# auxshiled1_8b.net
KiCad netlist of a schematic drawn in EAGLE
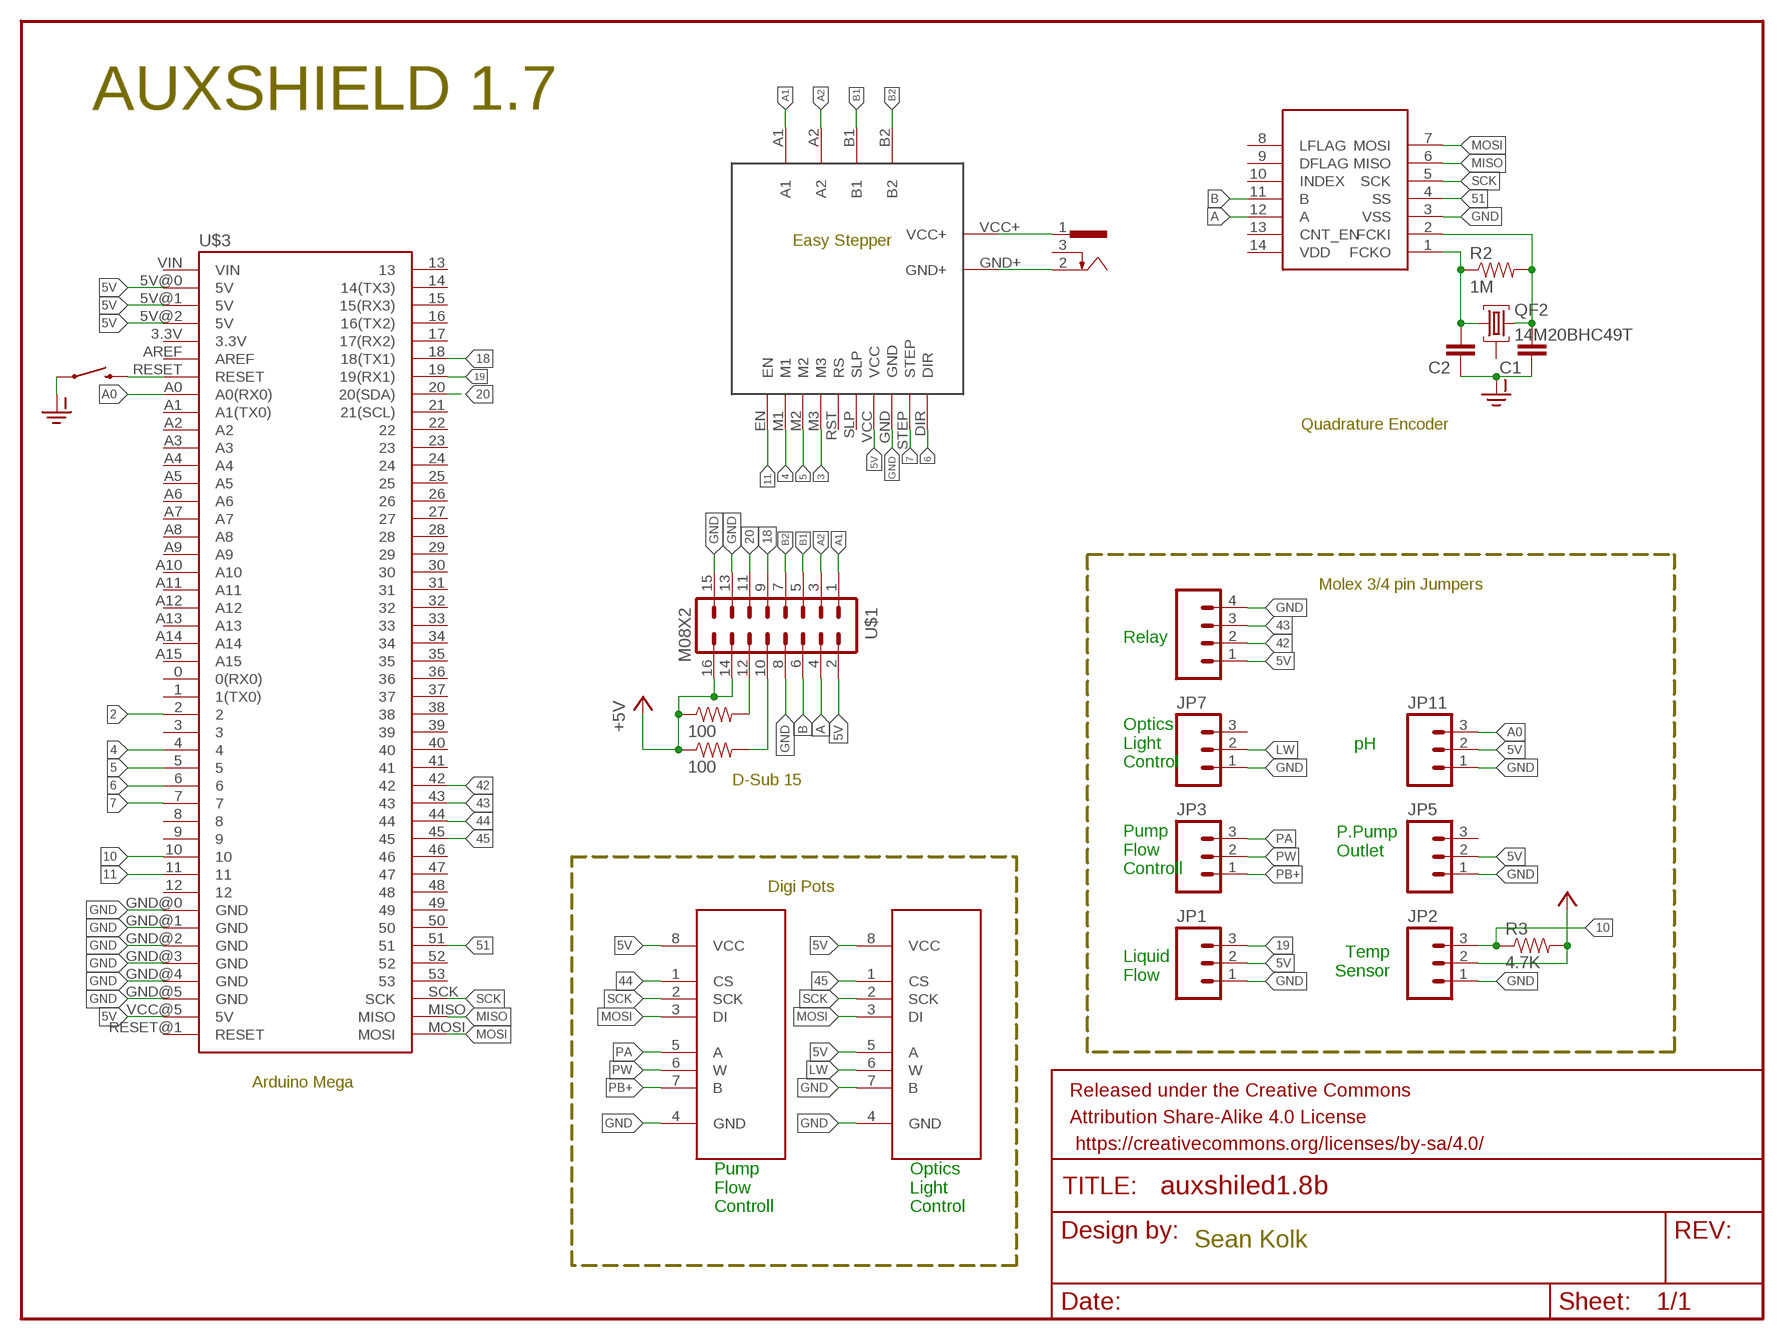
[diagram p0: schematic, sheet 1]

(export (version "E")
  (design (tool "Eeschema 10.0.6"))
  (components
    (comp (ref "C1")
      (value "0.1UF-50V-20%(PTH)KIT-EZ")
      (footprint "eagle-import:CAP-PTH-SMALL-KIT")
      (libsource (lib "eagle-import") (part "0.1UF-50V-20%(PTH)KIT-EZ"))
    )
    (comp (ref "C2")
      (value "0.1UF-50V-20%(PTH)KIT-EZ")
      (footprint "eagle-import:CAP-PTH-SMALL-KIT")
      (libsource (lib "eagle-import") (part "0.1UF-50V-20%(PTH)KIT-EZ"))
    )
    (comp (ref "FRAME1")
      (value "FRAME-LETTER")
      (footprint "eagle-import:CREATIVE_COMMONS")
      (libsource (lib "eagle-import") (part "FRAME-LETTER"))
    )
    (comp (ref "JP1")
      (value "M03POLAR")
      (footprint "eagle-import:MOLEX-1X3")
      (libsource (lib "eagle-import") (part "M03POLAR"))
    )
    (comp (ref "JP2")
      (value "M03POLAR")
      (footprint "eagle-import:MOLEX-1X3")
      (libsource (lib "eagle-import") (part "M03POLAR"))
    )
    (comp (ref "JP3")
      (value "M03POLAR")
      (footprint "eagle-import:MOLEX-1X3")
      (libsource (lib "eagle-import") (part "M03POLAR"))
    )
    (comp (ref "JP5")
      (value "M03POLAR")
      (footprint "eagle-import:MOLEX-1X3")
      (libsource (lib "eagle-import") (part "M03POLAR"))
    )
    (comp (ref "JP7")
      (value "M03POLAR")
      (footprint "eagle-import:MOLEX-1X3")
      (libsource (lib "eagle-import") (part "M03POLAR"))
    )
    (comp (ref "JP11")
      (value "M03POLAR")
      (footprint "eagle-import:MOLEX-1X3")
      (libsource (lib "eagle-import") (part "M03POLAR"))
    )
    (comp (ref "PUMPDIGIPOT")
      (value "MCP41XXXDIL")
      (footprint "eagle-import:DIL-08")
      (libsource (lib "eagle-import") (part "MCP41XXXDIL"))
    )
    (comp (ref "QF2")
      (value "14M20BHC49T")
      (footprint "eagle-import:HC49U")
      (libsource (lib "eagle-import") (part "14M20BHC49T"))
    )
    (comp (ref "R1")
      (value "100")
      (footprint "eagle-import:AXIAL-0.3")
      (libsource (lib "eagle-import") (part "10OHM-1/4W-5%(PTH)"))
    )
    (comp (ref "R2")
      (value "1M")
      (footprint "eagle-import:AXIAL-0.3")
      (libsource (lib "eagle-import") (part "10OHM-1/4W-5%(PTH)"))
    )
    (comp (ref "R3")
      (value "4.7K")
      (footprint "eagle-import:AXIAL-0.3")
      (libsource (lib "eagle-import") (part "10OHM-1/4W-5%(PTH)"))
    )
    (comp (ref "R4")
      (value "100")
      (footprint "eagle-import:AXIAL-0.3")
      (libsource (lib "eagle-import") (part "10OHM-1/4W-5%(PTH)"))
    )
    (comp (ref "RELAY")
      (value "M04POLAR")
      (footprint "eagle-import:MOLEX-1X4")
      (libsource (lib "eagle-import") (part "M04POLAR"))
    )
    (comp (ref "S1")
      (value "SWITCH-MOMENTARY-2PTH_EZ")
      (footprint "eagle-import:TACTILE-PTH-EZ")
      (libsource (lib "eagle-import") (part "SWITCH-MOMENTARY-2PTH_EZ"))
    )
    (comp (ref "U$1")
      (value "M08X2")
      (footprint "eagle-import:2X8")
      (libsource (lib "eagle-import") (part "M08X2"))
    )
    (comp (ref "U$2")
      (value "LS7366R")
      (footprint "eagle-import:SO014")
      (libsource (lib "eagle-import") (part "LS7366R"))
    )
    (comp (ref "U$3")
      (value "ARDUINO-MEGA-V2")
      (footprint "eagle-import:ARDUINO_MEGA-PRO-5V")
      (libsource (lib "eagle-import") (part "ARDUINO-MEGA-V2"))
    )
    (comp (ref "U$4")
      (value "BIG_EASY_DRIVER")
      (footprint "eagle-import:BIG_EASY_DRIVER_PACK")
      (libsource (lib "eagle-import") (part "BIG_EASY_DRIVER"))
    )
    (comp (ref "U1")
      (value "MCP41XXXDIL")
      (footprint "eagle-import:DIL-08")
      (libsource (lib "eagle-import") (part "MCP41XXXDIL"))
    )
    (comp (ref "X1")
      (value "SCD-014A")
      (footprint "eagle-import:SCD-014-A")
      (libsource (lib "eagle-import") (part "SCD-014A"))
    )
  )
  (nets
    (net (code "1") (name "+5V") (class "Default")
      (node (ref "JP2") (pin "2") (pinfunction "2_2") (pintype "passive"))
      (node (ref "R1") (pin "P$1") (pinfunction "1_P$1") (pintype "passive"))
      (node (ref "R3") (pin "P$2") (pinfunction "2_P$2") (pintype "passive"))
      (node (ref "R4") (pin "P$1") (pinfunction "1_P$1") (pintype "passive"))
      (node (ref "U$1") (pin "14") (pinfunction "14_14") (pintype "passive"))
      (node (ref "U$1") (pin "16") (pinfunction "16_16") (pintype "passive"))
    )
    (net (code "2") (name "2") (class "Default")
      (node (ref "U$3") (pin "2") (pinfunction "2_2") (pintype "bidirectional"))
    )
    (net (code "3") (name "3") (class "Default")
      (node (ref "U$4") (pin "M3") (pinfunction "M3_M3") (pintype "bidirectional"))
    )
    (net (code "4") (name "4") (class "Default")
      (node (ref "U$3") (pin "4") (pinfunction "4_4") (pintype "bidirectional"))
      (node (ref "U$4") (pin "M1") (pinfunction "M1_M1") (pintype "bidirectional"))
    )
    (net (code "5") (name "5") (class "Default")
      (node (ref "U$3") (pin "5") (pinfunction "5_5") (pintype "bidirectional"))
      (node (ref "U$4") (pin "M2") (pinfunction "M2_M2") (pintype "bidirectional"))
    )
    (net (code "6") (name "5V") (class "Default")
      (node (ref "JP1") (pin "2") (pinfunction "2_2") (pintype "passive"))
      (node (ref "JP11") (pin "2") (pinfunction "2_2") (pintype "passive"))
      (node (ref "JP5") (pin "2") (pinfunction "2_2") (pintype "passive"))
      (node (ref "PUMPDIGIPOT") (pin "8") (pinfunction "VCC_8") (pintype "bidirectional"))
      (node (ref "RELAY") (pin "1") (pinfunction "1_1") (pintype "passive"))
      (node (ref "U$1") (pin "2") (pinfunction "2_2") (pintype "passive"))
      (node (ref "U$3") (pin "5V@0") (pinfunction "5V_5V@0") (pintype "bidirectional"))
      (node (ref "U$3") (pin "5V@1") (pinfunction "5V_5V@1") (pintype "bidirectional"))
      (node (ref "U$3") (pin "5V@2") (pinfunction "5V_5V@2") (pintype "bidirectional"))
      (node (ref "U$3") (pin "VCC@5") (pinfunction "5V_VCC@5") (pintype "bidirectional"))
      (node (ref "U$4") (pin "VCC") (pinfunction "VCC_VCC") (pintype "bidirectional"))
      (node (ref "U1") (pin "5") (pinfunction "A_5") (pintype "bidirectional"))
      (node (ref "U1") (pin "8") (pinfunction "VCC_8") (pintype "bidirectional"))
    )
    (net (code "7") (name "6") (class "Default")
      (node (ref "U$3") (pin "6") (pinfunction "6_6") (pintype "bidirectional"))
      (node (ref "U$4") (pin "DIR") (pinfunction "DIR_DIR") (pintype "bidirectional"))
    )
    (net (code "8") (name "7") (class "Default")
      (node (ref "U$3") (pin "7") (pinfunction "7_7") (pintype "bidirectional"))
      (node (ref "U$4") (pin "STEP") (pinfunction "STEP_STEP") (pintype "bidirectional"))
    )
    (net (code "9") (name "10") (class "Default")
      (node (ref "JP2") (pin "3") (pinfunction "3_3") (pintype "passive"))
      (node (ref "R3") (pin "P$1") (pinfunction "1_P$1") (pintype "passive"))
      (node (ref "U$3") (pin "10") (pinfunction "10_10") (pintype "bidirectional"))
    )
    (net (code "10") (name "11") (class "Default")
      (node (ref "U$3") (pin "11") (pinfunction "11_11") (pintype "bidirectional"))
      (node (ref "U$4") (pin "EN") (pinfunction "EN_EN") (pintype "bidirectional"))
    )
    (net (code "11") (name "18") (class "Default")
      (node (ref "U$1") (pin "9") (pinfunction "9_9") (pintype "passive"))
      (node (ref "U$3") (pin "18") (pinfunction "18(TX1)_18") (pintype "bidirectional"))
    )
    (net (code "12") (name "19") (class "Default")
      (node (ref "JP1") (pin "3") (pinfunction "3_3") (pintype "passive"))
      (node (ref "U$3") (pin "19") (pinfunction "19(RX1)_19") (pintype "bidirectional"))
    )
    (net (code "13") (name "20") (class "Default")
      (node (ref "U$1") (pin "11") (pinfunction "11_11") (pintype "passive"))
      (node (ref "U$3") (pin "20") (pinfunction "20(SDA)_20") (pintype "bidirectional"))
    )
    (net (code "14") (name "42") (class "Default")
      (node (ref "RELAY") (pin "2") (pinfunction "2_2") (pintype "passive"))
      (node (ref "U$3") (pin "42") (pinfunction "42_42") (pintype "bidirectional"))
    )
    (net (code "15") (name "43") (class "Default")
      (node (ref "RELAY") (pin "3") (pinfunction "3_3") (pintype "passive"))
      (node (ref "U$3") (pin "43") (pinfunction "43_43") (pintype "bidirectional"))
    )
    (net (code "16") (name "44") (class "Default")
      (node (ref "PUMPDIGIPOT") (pin "1") (pinfunction "CS_1") (pintype "bidirectional"))
      (node (ref "U$3") (pin "44") (pinfunction "44_44") (pintype "bidirectional"))
    )
    (net (code "17") (name "45") (class "Default")
      (node (ref "U$3") (pin "45") (pinfunction "45_45") (pintype "bidirectional"))
      (node (ref "U1") (pin "1") (pinfunction "CS_1") (pintype "bidirectional"))
    )
    (net (code "18") (name "51") (class "Default")
      (node (ref "U$2") (pin "4") (pinfunction "SS_4") (pintype "bidirectional"))
      (node (ref "U$3") (pin "51") (pinfunction "51_51") (pintype "bidirectional"))
    )
    (net (code "19") (name "A") (class "Default")
      (node (ref "U$1") (pin "4") (pinfunction "4_4") (pintype "passive"))
      (node (ref "U$2") (pin "12") (pinfunction "A_12") (pintype "bidirectional"))
    )
    (net (code "20") (name "A0") (class "Default")
      (node (ref "JP11") (pin "3") (pinfunction "3_3") (pintype "passive"))
      (node (ref "U$3") (pin "A0") (pinfunction "A0(RX0)_A0") (pintype "bidirectional"))
    )
    (net (code "21") (name "A1") (class "Default")
      (node (ref "U$1") (pin "1") (pinfunction "1_1") (pintype "passive"))
      (node (ref "U$4") (pin "A1") (pinfunction "A1_A1") (pintype "bidirectional"))
    )
    (net (code "22") (name "A2") (class "Default")
      (node (ref "U$1") (pin "3") (pinfunction "3_3") (pintype "passive"))
      (node (ref "U$4") (pin "A2") (pinfunction "A2_A2") (pintype "bidirectional"))
    )
    (net (code "23") (name "B") (class "Default")
      (node (ref "U$1") (pin "6") (pinfunction "6_6") (pintype "passive"))
      (node (ref "U$2") (pin "11") (pinfunction "B_11") (pintype "bidirectional"))
    )
    (net (code "24") (name "B1") (class "Default")
      (node (ref "U$1") (pin "5") (pinfunction "5_5") (pintype "passive"))
      (node (ref "U$4") (pin "B1") (pinfunction "B1_B1") (pintype "bidirectional"))
    )
    (net (code "25") (name "B2") (class "Default")
      (node (ref "U$1") (pin "7") (pinfunction "7_7") (pintype "passive"))
      (node (ref "U$4") (pin "B2") (pinfunction "B2_B2") (pintype "bidirectional"))
    )
    (net (code "26") (name "GND") (class "Default")
      (node (ref "JP1") (pin "1") (pinfunction "1_1") (pintype "passive"))
      (node (ref "JP11") (pin "1") (pinfunction "1_1") (pintype "passive"))
      (node (ref "JP2") (pin "1") (pinfunction "1_1") (pintype "passive"))
      (node (ref "JP5") (pin "1") (pinfunction "1_1") (pintype "passive"))
      (node (ref "JP7") (pin "1") (pinfunction "1_1") (pintype "passive"))
      (node (ref "PUMPDIGIPOT") (pin "4") (pinfunction "GND_4") (pintype "bidirectional"))
      (node (ref "RELAY") (pin "4") (pinfunction "4_4") (pintype "passive"))
      (node (ref "U$1") (pin "13") (pinfunction "13_13") (pintype "passive"))
      (node (ref "U$1") (pin "15") (pinfunction "15_15") (pintype "passive"))
      (node (ref "U$1") (pin "8") (pinfunction "8_8") (pintype "passive"))
      (node (ref "U$2") (pin "3") (pinfunction "VSS_3") (pintype "bidirectional"))
      (node (ref "U$3") (pin "GND@0") (pinfunction "GND_GND@0") (pintype "bidirectional"))
      (node (ref "U$3") (pin "GND@1") (pinfunction "GND_GND@1") (pintype "bidirectional"))
      (node (ref "U$3") (pin "GND@2") (pinfunction "GND_GND@2") (pintype "bidirectional"))
      (node (ref "U$3") (pin "GND@3") (pinfunction "GND_GND@3") (pintype "bidirectional"))
      (node (ref "U$3") (pin "GND@4") (pinfunction "GND_GND@4") (pintype "bidirectional"))
      (node (ref "U$3") (pin "GND@5") (pinfunction "GND_GND@5") (pintype "bidirectional"))
      (node (ref "U$4") (pin "GND") (pinfunction "GND_GND") (pintype "bidirectional"))
      (node (ref "U1") (pin "4") (pinfunction "GND_4") (pintype "bidirectional"))
      (node (ref "U1") (pin "7") (pinfunction "B_7") (pintype "bidirectional"))
    )
    (net (code "27") (name "GND-ISO") (class "Default")
      (node (ref "C1") (pin "1") (pinfunction "1_1") (pintype "passive"))
      (node (ref "C2") (pin "1") (pinfunction "1_1") (pintype "passive"))
      (node (ref "S1") (pin "1") (pinfunction "1_1") (pintype "passive"))
    )
    (net (code "28") (name "LW") (class "Default")
      (node (ref "JP7") (pin "2") (pinfunction "2_2") (pintype "passive"))
      (node (ref "U1") (pin "6") (pinfunction "W_6") (pintype "bidirectional"))
    )
    (net (code "29") (name "MISO") (class "Default")
      (node (ref "U$2") (pin "6") (pinfunction "MISO_6") (pintype "bidirectional"))
      (node (ref "U$3") (pin "MISO") (pinfunction "MISO_MISO") (pintype "bidirectional"))
    )
    (net (code "30") (name "MOSI") (class "Default")
      (node (ref "PUMPDIGIPOT") (pin "3") (pinfunction "DI_3") (pintype "bidirectional"))
      (node (ref "U$2") (pin "7") (pinfunction "MOSI_7") (pintype "bidirectional"))
      (node (ref "U$3") (pin "MOSI") (pinfunction "MOSI_MOSI") (pintype "bidirectional"))
      (node (ref "U1") (pin "3") (pinfunction "DI_3") (pintype "bidirectional"))
    )
    (net (code "31") (name "Net-(R1-2)") (class "Default")
      (node (ref "R1") (pin "P$2") (pinfunction "2_P$2") (pintype "passive"))
      (node (ref "U$1") (pin "10") (pinfunction "10_10") (pintype "passive"))
    )
    (net (code "32") (name "Net-(R2-1)") (class "Default")
      (node (ref "C2") (pin "2") (pinfunction "2_2") (pintype "passive"))
      (node (ref "QF2") (pin "1") (pinfunction "1_1") (pintype "passive"))
      (node (ref "R2") (pin "P$1") (pinfunction "1_P$1") (pintype "passive"))
      (node (ref "U$2") (pin "1") (pinfunction "FCKO_1") (pintype "bidirectional"))
    )
    (net (code "33") (name "Net-(R2-2)") (class "Default")
      (node (ref "C1") (pin "2") (pinfunction "2_2") (pintype "passive"))
      (node (ref "QF2") (pin "3") (pinfunction "3_3") (pintype "passive"))
      (node (ref "R2") (pin "P$2") (pinfunction "2_P$2") (pintype "passive"))
      (node (ref "U$2") (pin "2") (pinfunction "FCKI_2") (pintype "bidirectional"))
    )
    (net (code "34") (name "Net-(R4-2)") (class "Default")
      (node (ref "R4") (pin "P$2") (pinfunction "2_P$2") (pintype "passive"))
      (node (ref "U$1") (pin "12") (pinfunction "12_12") (pintype "passive"))
    )
    (net (code "35") (name "Net-(S1-2)") (class "Default")
      (node (ref "S1") (pin "3") (pinfunction "2_3") (pintype "passive"))
      (node (ref "U$3") (pin "RESET") (pinfunction "RESET_RESET") (pintype "bidirectional"))
    )
    (net (code "36") (name "Net-(U$4-PadGND+)") (class "Default")
      (node (ref "U$4") (pin "GND+") (pinfunction "GND+_GND+") (pintype "bidirectional"))
      (node (ref "X1") (pin "2") (pinfunction "2_2") (pintype "passive"))
    )
    (net (code "37") (name "Net-(U$4-PadVCC+)") (class "Default")
      (node (ref "U$4") (pin "VCC+") (pinfunction "VCC+_VCC+") (pintype "bidirectional"))
      (node (ref "X1") (pin "1") (pinfunction "1_1") (pintype "passive"))
    )
    (net (code "38") (name "PA") (class "Default")
      (node (ref "JP3") (pin "3") (pinfunction "3_3") (pintype "passive"))
      (node (ref "PUMPDIGIPOT") (pin "5") (pinfunction "A_5") (pintype "bidirectional"))
    )
    (net (code "39") (name "PB+") (class "Default")
      (node (ref "JP3") (pin "1") (pinfunction "1_1") (pintype "passive"))
      (node (ref "PUMPDIGIPOT") (pin "7") (pinfunction "B_7") (pintype "bidirectional"))
    )
    (net (code "40") (name "PW") (class "Default")
      (node (ref "JP3") (pin "2") (pinfunction "2_2") (pintype "passive"))
      (node (ref "PUMPDIGIPOT") (pin "6") (pinfunction "W_6") (pintype "bidirectional"))
    )
    (net (code "41") (name "SCK") (class "Default")
      (node (ref "PUMPDIGIPOT") (pin "2") (pinfunction "SCK_2") (pintype "bidirectional"))
      (node (ref "U$2") (pin "5") (pinfunction "SCK_5") (pintype "bidirectional"))
      (node (ref "U$3") (pin "SCK") (pinfunction "SCK_SCK") (pintype "bidirectional"))
      (node (ref "U1") (pin "2") (pinfunction "SCK_2") (pintype "bidirectional"))
    )
    (net (code "42") (name "unconnected-(JP5-Pad3)") (class "Default")
      (node (ref "JP5") (pin "3") (pinfunction "3_3") (pintype "passive"))
    )
    (net (code "43") (name "unconnected-(JP7-Pad3)") (class "Default")
      (node (ref "JP7") (pin "3") (pinfunction "3_3") (pintype "passive"))
    )
    (net (code "44") (name "unconnected-(QF2-Pad2)") (class "Default")
      (node (ref "QF2") (pin "2") (pinfunction "2_2") (pintype "passive"))
    )
    (net (code "45") (name "unconnected-(U$2-CNT_EN-Pad13)") (class "Default")
      (node (ref "U$2") (pin "13") (pinfunction "CNT_EN_13") (pintype "bidirectional"))
    )
    (net (code "46") (name "unconnected-(U$2-DFLAG-Pad9)") (class "Default")
      (node (ref "U$2") (pin "9") (pinfunction "DFLAG_9") (pintype "bidirectional"))
    )
    (net (code "47") (name "unconnected-(U$2-INDEX-Pad10)") (class "Default")
      (node (ref "U$2") (pin "10") (pinfunction "INDEX_10") (pintype "bidirectional"))
    )
    (net (code "48") (name "unconnected-(U$2-LFLAG-Pad8)") (class "Default")
      (node (ref "U$2") (pin "8") (pinfunction "LFLAG_8") (pintype "bidirectional"))
    )
    (net (code "49") (name "unconnected-(U$2-VDD-Pad14)") (class "Default")
      (node (ref "U$2") (pin "14") (pinfunction "VDD_14") (pintype "bidirectional"))
    )
    (net (code "50") (name "unconnected-(U$3-0(RX0)-Pad0)") (class "Default")
      (node (ref "U$3") (pin "0") (pinfunction "0(RX0)_0") (pintype "bidirectional"))
    )
    (net (code "51") (name "unconnected-(U$3-1(TX0)-Pad1)") (class "Default")
      (node (ref "U$3") (pin "1") (pinfunction "1(TX0)_1") (pintype "bidirectional"))
    )
    (net (code "52") (name "unconnected-(U$3-14(TX3)-Pad14)") (class "Default")
      (node (ref "U$3") (pin "14") (pinfunction "14(TX3)_14") (pintype "bidirectional"))
    )
    (net (code "53") (name "unconnected-(U$3-15(RX3)-Pad15)") (class "Default")
      (node (ref "U$3") (pin "15") (pinfunction "15(RX3)_15") (pintype "bidirectional"))
    )
    (net (code "54") (name "unconnected-(U$3-16(TX2)-Pad16)") (class "Default")
      (node (ref "U$3") (pin "16") (pinfunction "16(TX2)_16") (pintype "bidirectional"))
    )
    (net (code "55") (name "unconnected-(U$3-17(RX2)-Pad17)") (class "Default")
      (node (ref "U$3") (pin "17") (pinfunction "17(RX2)_17") (pintype "bidirectional"))
    )
    (net (code "56") (name "unconnected-(U$3-21(SCL)-Pad21)") (class "Default")
      (node (ref "U$3") (pin "21") (pinfunction "21(SCL)_21") (pintype "bidirectional"))
    )
    (net (code "57") (name "unconnected-(U$3-A1(TX0)-PadA1)") (class "Default")
      (node (ref "U$3") (pin "A1") (pinfunction "A1(TX0)_A1") (pintype "bidirectional"))
    )
    (net (code "58") (name "unconnected-(U$3-Pad3)") (class "Default")
      (node (ref "U$3") (pin "3") (pinfunction "3_3") (pintype "bidirectional"))
    )
    (net (code "59") (name "unconnected-(U$3-Pad3.3V)") (class "Default")
      (node (ref "U$3") (pin "3.3V") (pinfunction "3.3V_3.3V") (pintype "bidirectional"))
    )
    (net (code "60") (name "unconnected-(U$3-Pad8)") (class "Default")
      (node (ref "U$3") (pin "8") (pinfunction "8_8") (pintype "bidirectional"))
    )
    (net (code "61") (name "unconnected-(U$3-Pad9)") (class "Default")
      (node (ref "U$3") (pin "9") (pinfunction "9_9") (pintype "bidirectional"))
    )
    (net (code "62") (name "unconnected-(U$3-Pad12)") (class "Default")
      (node (ref "U$3") (pin "12") (pinfunction "12_12") (pintype "bidirectional"))
    )
    (net (code "63") (name "unconnected-(U$3-Pad13)") (class "Default")
      (node (ref "U$3") (pin "13") (pinfunction "13_13") (pintype "bidirectional"))
    )
    (net (code "64") (name "unconnected-(U$3-Pad22)") (class "Default")
      (node (ref "U$3") (pin "22") (pinfunction "22_22") (pintype "bidirectional"))
    )
    (net (code "65") (name "unconnected-(U$3-Pad23)") (class "Default")
      (node (ref "U$3") (pin "23") (pinfunction "23_23") (pintype "bidirectional"))
    )
    (net (code "66") (name "unconnected-(U$3-Pad24)") (class "Default")
      (node (ref "U$3") (pin "24") (pinfunction "24_24") (pintype "bidirectional"))
    )
    (net (code "67") (name "unconnected-(U$3-Pad25)") (class "Default")
      (node (ref "U$3") (pin "25") (pinfunction "25_25") (pintype "bidirectional"))
    )
    (net (code "68") (name "unconnected-(U$3-Pad26)") (class "Default")
      (node (ref "U$3") (pin "26") (pinfunction "26_26") (pintype "bidirectional"))
    )
    (net (code "69") (name "unconnected-(U$3-Pad27)") (class "Default")
      (node (ref "U$3") (pin "27") (pinfunction "27_27") (pintype "bidirectional"))
    )
    (net (code "70") (name "unconnected-(U$3-Pad28)") (class "Default")
      (node (ref "U$3") (pin "28") (pinfunction "28_28") (pintype "bidirectional"))
    )
    (net (code "71") (name "unconnected-(U$3-Pad29)") (class "Default")
      (node (ref "U$3") (pin "29") (pinfunction "29_29") (pintype "bidirectional"))
    )
    (net (code "72") (name "unconnected-(U$3-Pad30)") (class "Default")
      (node (ref "U$3") (pin "30") (pinfunction "30_30") (pintype "bidirectional"))
    )
    (net (code "73") (name "unconnected-(U$3-Pad31)") (class "Default")
      (node (ref "U$3") (pin "31") (pinfunction "31_31") (pintype "bidirectional"))
    )
    (net (code "74") (name "unconnected-(U$3-Pad32)") (class "Default")
      (node (ref "U$3") (pin "32") (pinfunction "32_32") (pintype "bidirectional"))
    )
    (net (code "75") (name "unconnected-(U$3-Pad33)") (class "Default")
      (node (ref "U$3") (pin "33") (pinfunction "33_33") (pintype "bidirectional"))
    )
    (net (code "76") (name "unconnected-(U$3-Pad34)") (class "Default")
      (node (ref "U$3") (pin "34") (pinfunction "34_34") (pintype "bidirectional"))
    )
    (net (code "77") (name "unconnected-(U$3-Pad35)") (class "Default")
      (node (ref "U$3") (pin "35") (pinfunction "35_35") (pintype "bidirectional"))
    )
    (net (code "78") (name "unconnected-(U$3-Pad36)") (class "Default")
      (node (ref "U$3") (pin "36") (pinfunction "36_36") (pintype "bidirectional"))
    )
    (net (code "79") (name "unconnected-(U$3-Pad37)") (class "Default")
      (node (ref "U$3") (pin "37") (pinfunction "37_37") (pintype "bidirectional"))
    )
    (net (code "80") (name "unconnected-(U$3-Pad38)") (class "Default")
      (node (ref "U$3") (pin "38") (pinfunction "38_38") (pintype "bidirectional"))
    )
    (net (code "81") (name "unconnected-(U$3-Pad39)") (class "Default")
      (node (ref "U$3") (pin "39") (pinfunction "39_39") (pintype "bidirectional"))
    )
    (net (code "82") (name "unconnected-(U$3-Pad40)") (class "Default")
      (node (ref "U$3") (pin "40") (pinfunction "40_40") (pintype "bidirectional"))
    )
    (net (code "83") (name "unconnected-(U$3-Pad41)") (class "Default")
      (node (ref "U$3") (pin "41") (pinfunction "41_41") (pintype "bidirectional"))
    )
    (net (code "84") (name "unconnected-(U$3-Pad46)") (class "Default")
      (node (ref "U$3") (pin "46") (pinfunction "46_46") (pintype "bidirectional"))
    )
    (net (code "85") (name "unconnected-(U$3-Pad47)") (class "Default")
      (node (ref "U$3") (pin "47") (pinfunction "47_47") (pintype "bidirectional"))
    )
    (net (code "86") (name "unconnected-(U$3-Pad48)") (class "Default")
      (node (ref "U$3") (pin "48") (pinfunction "48_48") (pintype "bidirectional"))
    )
    (net (code "87") (name "unconnected-(U$3-Pad49)") (class "Default")
      (node (ref "U$3") (pin "49") (pinfunction "49_49") (pintype "bidirectional"))
    )
    (net (code "88") (name "unconnected-(U$3-Pad50)") (class "Default")
      (node (ref "U$3") (pin "50") (pinfunction "50_50") (pintype "bidirectional"))
    )
    (net (code "89") (name "unconnected-(U$3-Pad52)") (class "Default")
      (node (ref "U$3") (pin "52") (pinfunction "52_52") (pintype "bidirectional"))
    )
    (net (code "90") (name "unconnected-(U$3-Pad53)") (class "Default")
      (node (ref "U$3") (pin "53") (pinfunction "53_53") (pintype "bidirectional"))
    )
    (net (code "91") (name "unconnected-(U$3-PadA2)") (class "Default")
      (node (ref "U$3") (pin "A2") (pinfunction "A2_A2") (pintype "bidirectional"))
    )
    (net (code "92") (name "unconnected-(U$3-PadA3)") (class "Default")
      (node (ref "U$3") (pin "A3") (pinfunction "A3_A3") (pintype "bidirectional"))
    )
    (net (code "93") (name "unconnected-(U$3-PadA4)") (class "Default")
      (node (ref "U$3") (pin "A4") (pinfunction "A4_A4") (pintype "bidirectional"))
    )
    (net (code "94") (name "unconnected-(U$3-PadA5)") (class "Default")
      (node (ref "U$3") (pin "A5") (pinfunction "A5_A5") (pintype "bidirectional"))
    )
    (net (code "95") (name "unconnected-(U$3-PadA6)") (class "Default")
      (node (ref "U$3") (pin "A6") (pinfunction "A6_A6") (pintype "bidirectional"))
    )
    (net (code "96") (name "unconnected-(U$3-PadA7)") (class "Default")
      (node (ref "U$3") (pin "A7") (pinfunction "A7_A7") (pintype "bidirectional"))
    )
    (net (code "97") (name "unconnected-(U$3-PadA8)") (class "Default")
      (node (ref "U$3") (pin "A8") (pinfunction "A8_A8") (pintype "bidirectional"))
    )
    (net (code "98") (name "unconnected-(U$3-PadA9)") (class "Default")
      (node (ref "U$3") (pin "A9") (pinfunction "A9_A9") (pintype "bidirectional"))
    )
    (net (code "99") (name "unconnected-(U$3-PadA10)") (class "Default")
      (node (ref "U$3") (pin "A10") (pinfunction "A10_A10") (pintype "bidirectional"))
    )
    (net (code "100") (name "unconnected-(U$3-PadA11)") (class "Default")
      (node (ref "U$3") (pin "A11") (pinfunction "A11_A11") (pintype "bidirectional"))
    )
    (net (code "101") (name "unconnected-(U$3-PadA12)") (class "Default")
      (node (ref "U$3") (pin "A12") (pinfunction "A12_A12") (pintype "bidirectional"))
    )
    (net (code "102") (name "unconnected-(U$3-PadA13)") (class "Default")
      (node (ref "U$3") (pin "A13") (pinfunction "A13_A13") (pintype "bidirectional"))
    )
    (net (code "103") (name "unconnected-(U$3-PadA14)") (class "Default")
      (node (ref "U$3") (pin "A14") (pinfunction "A14_A14") (pintype "bidirectional"))
    )
    (net (code "104") (name "unconnected-(U$3-PadA15)") (class "Default")
      (node (ref "U$3") (pin "A15") (pinfunction "A15_A15") (pintype "bidirectional"))
    )
    (net (code "105") (name "unconnected-(U$3-PadAREF)") (class "Default")
      (node (ref "U$3") (pin "AREF") (pinfunction "AREF_AREF") (pintype "bidirectional"))
    )
    (net (code "106") (name "unconnected-(U$3-PadVIN)") (class "Default")
      (node (ref "U$3") (pin "VIN") (pinfunction "VIN_VIN") (pintype "bidirectional"))
    )
    (net (code "107") (name "unconnected-(U$3-RESET-PadRESET@1)") (class "Default")
      (node (ref "U$3") (pin "RESET@1") (pinfunction "RESET_RESET@1") (pintype "bidirectional"))
    )
    (net (code "108") (name "unconnected-(U$4-PadSLP)") (class "Default")
      (node (ref "U$4") (pin "SLP") (pinfunction "SLP_SLP") (pintype "bidirectional"))
    )
    (net (code "109") (name "unconnected-(U$4-RS-PadRST)") (class "Default")
      (node (ref "U$4") (pin "RST") (pinfunction "RS_RST") (pintype "bidirectional"))
    )
    (net (code "110") (name "unconnected-(X1-Pad3)") (class "Default")
      (node (ref "X1") (pin "3") (pinfunction "3_3") (pintype "passive"))
    )
  )
)
